# Smart_spectacles_for_drowsiness.net
KiCad netlist of a schematic drawn in EasyEDA
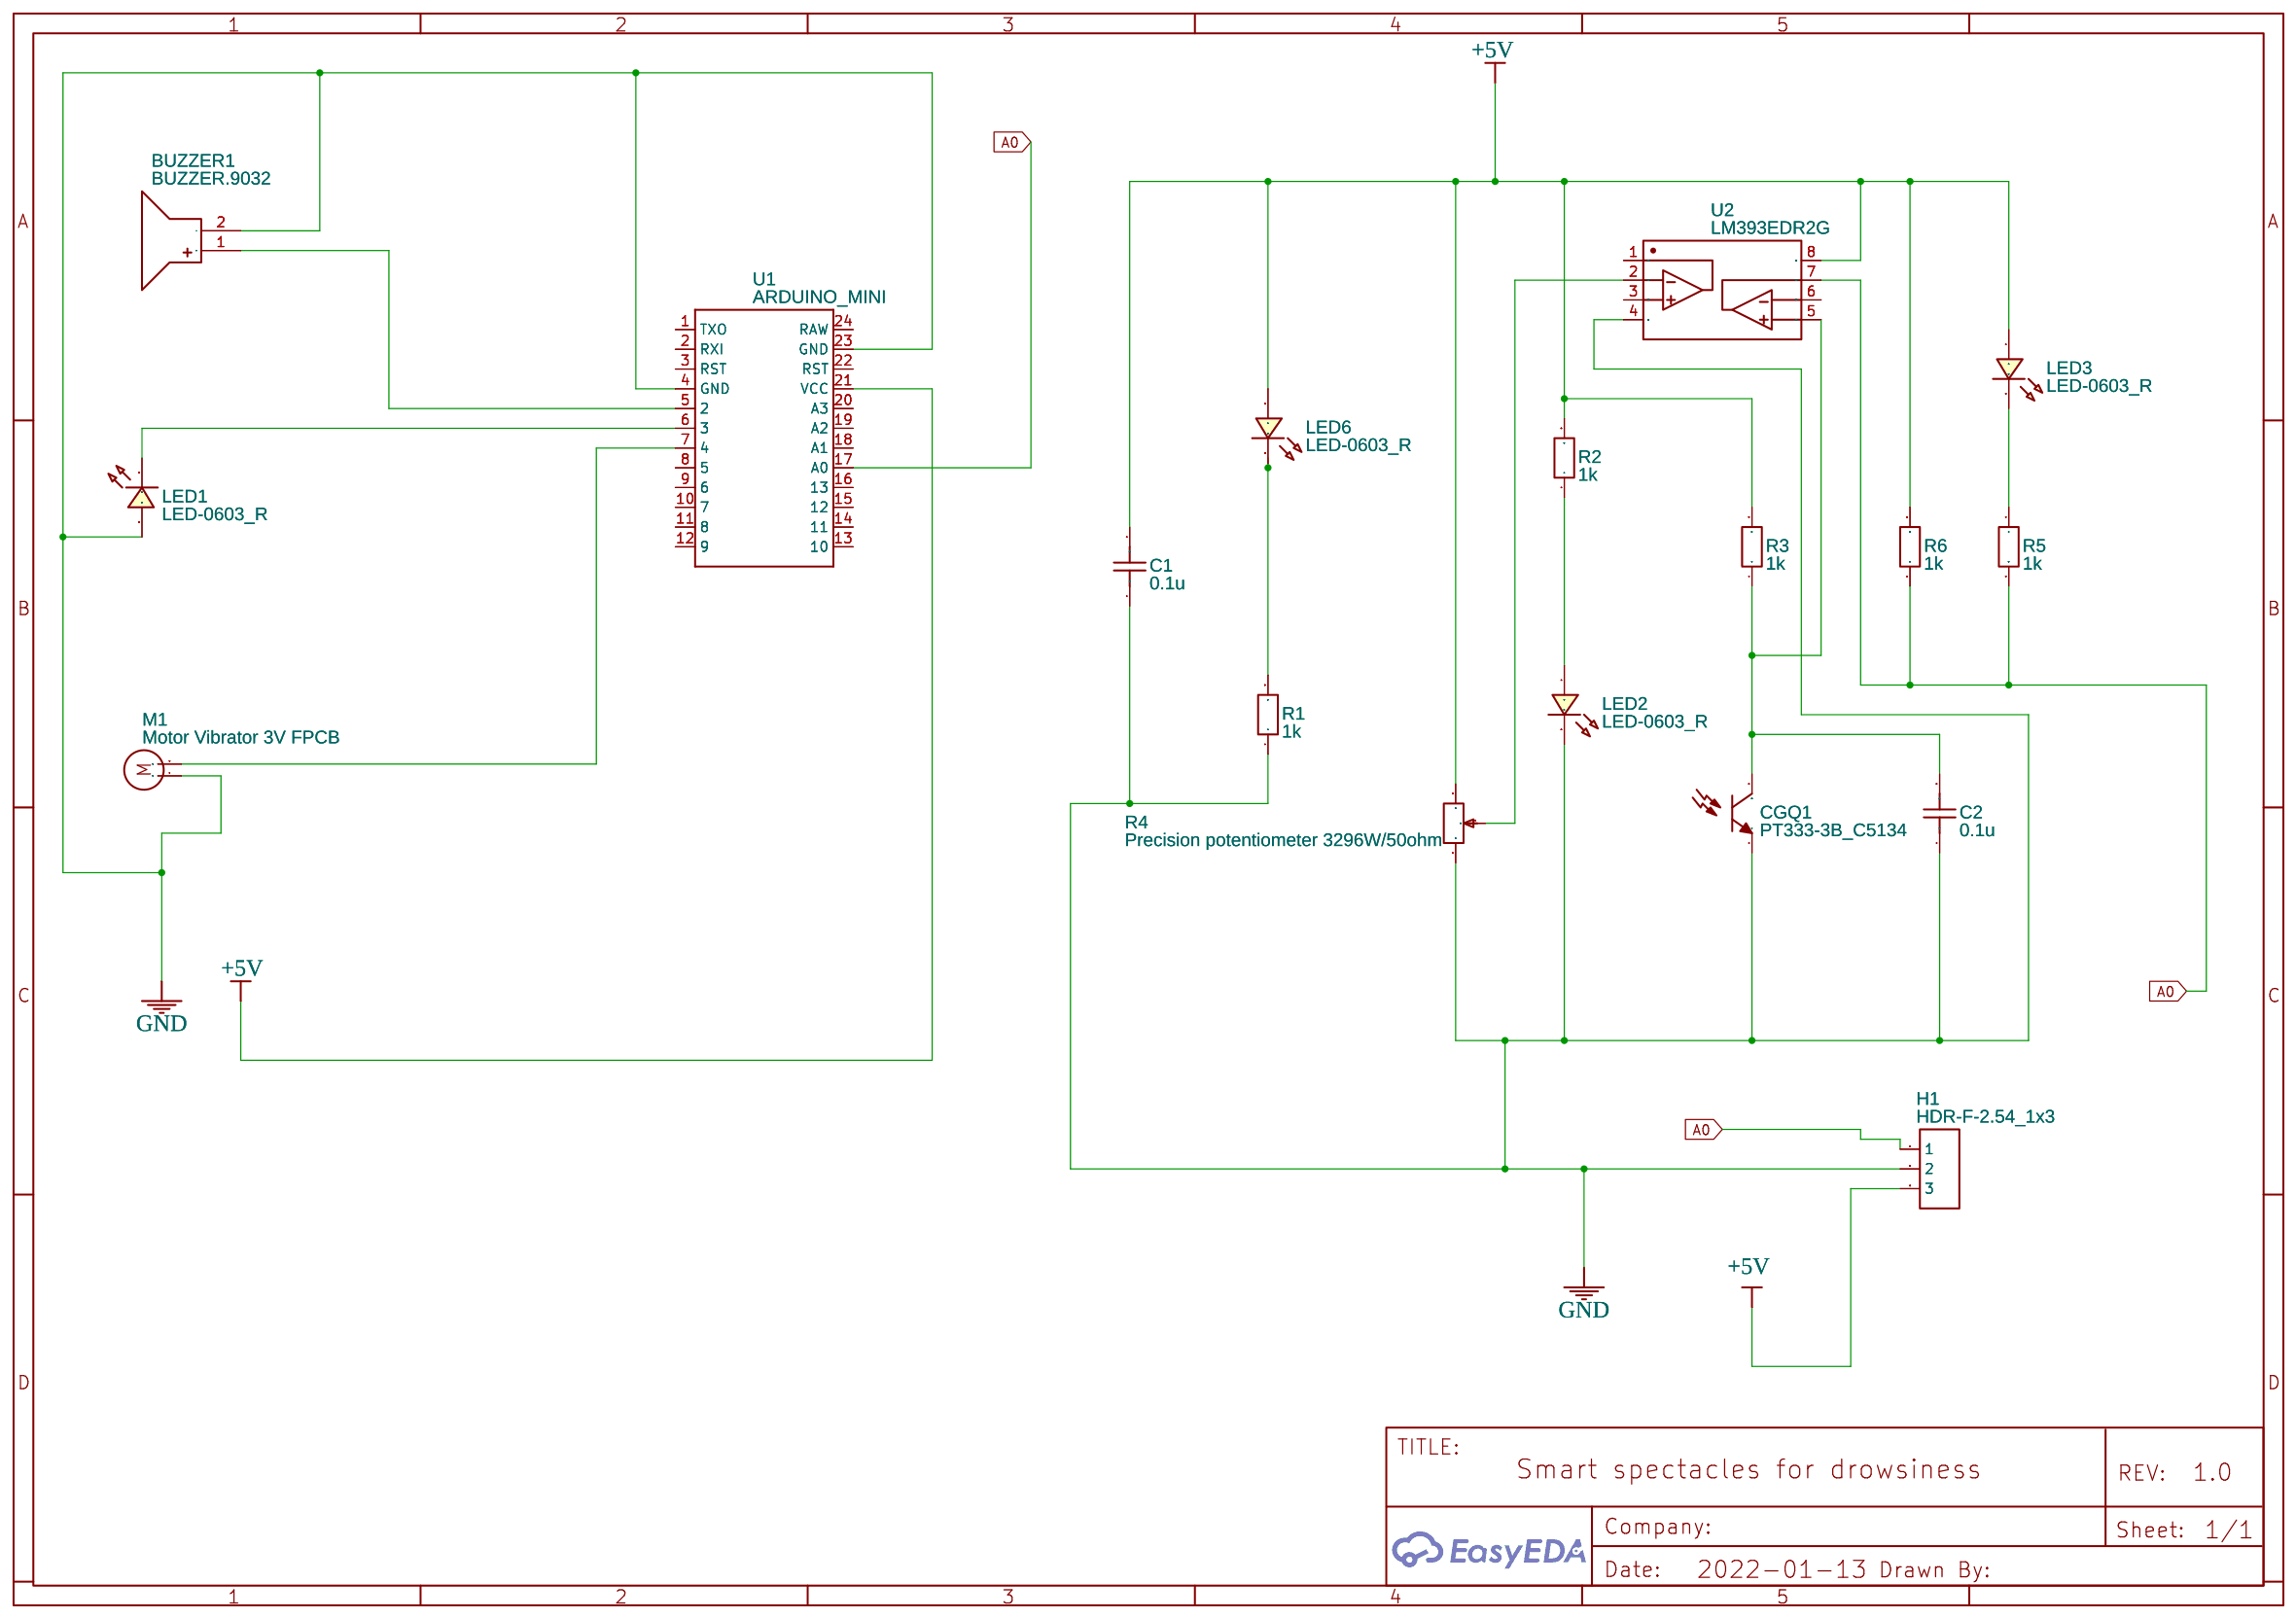
[diagram p0: schematic sheet]

(export (version "E")
  (design (tool "Eeschema 10.0.6"))
  (components
    (comp (ref "BUZZER1")
      (value "BUZZER.9032")
      (fields (field (name "BOM_Supplier Part") "C9900002564"))
      (libsource (lib "") (part "BUZZER.9032"))
    )
    (comp (ref "C1") (value "0.1u") (libsource (lib "") (part "C_0603_US")))
    (comp (ref "C2") (value "0.1u") (libsource (lib "") (part "C_0603_US")))
    (comp (ref "CGQ1")
      (value "PT333-3B_C5134")
      (fields (field (name "BOM_Manufacturer Part") "PT333-3B") (field (name "BOM_Supplier Part") "C5134"))
      (libsource (lib "") (part "PT333-3B_C5134"))
    )
    (comp (ref "H1")
      (value "HDR-F-2.54_1x3")
      (fields (field (name "BOM_Supplier Part") "C146690"))
      (libsource (lib "") (part "HDR-F-2.54_1x3"))
    )
    (comp (ref "LED1")
      (value "LED-0603_R")
      (fields
        (field (name "BOM_Manufacturer Part") "19-217/R6C-AL1M2VY/3T")
        (field (name "BOM_Supplier Part") "C72044")
      )
      (libsource (lib "") (part "LED-0603_R_1"))
    )
    (comp (ref "LED2")
      (value "LED-0603_R")
      (fields
        (field (name "BOM_Manufacturer Part") "19-217/R6C-AL1M2VY/3T")
        (field (name "BOM_Supplier Part") "C72044")
      )
      (libsource (lib "") (part "LED-0603_R"))
    )
    (comp (ref "LED3")
      (value "LED-0603_R")
      (fields
        (field (name "BOM_Manufacturer Part") "19-217/R6C-AL1M2VY/3T")
        (field (name "BOM_Supplier Part") "C72044")
      )
      (libsource (lib "") (part "LED-0603_R"))
    )
    (comp (ref "LED6")
      (value "LED-0603_R")
      (fields
        (field (name "BOM_Manufacturer Part") "19-217/R6C-AL1M2VY/3T")
        (field (name "BOM_Supplier Part") "C72044")
      )
      (libsource (lib "") (part "LED-0603_R"))
    )
    (comp (ref "M1")
      (value "Motor Vibrator 3V FPCB")
      (fields (field (name "BOM_Supplier Part") "C0827B020F"))
      (libsource (lib "") (part "Motor Vibrator 3V FPCB"))
    )
    (comp (ref "R1") (value "1k") (libsource (lib "") (part "R_0603_EU_1")))
    (comp (ref "R2") (value "1k") (libsource (lib "") (part "R_0603_EU_1")))
    (comp (ref "R3") (value "1k") (libsource (lib "") (part "R_0603_EU_1")))
    (comp (ref "R4")
      (value "Precision potentiometer 3296W/50ohm")
      (fields (field (name "BOM_Supplier Part") "C21881"))
      (libsource (lib "") (part "Precision potentiometer 3296W/50ohm"))
    )
    (comp (ref "R5") (value "1k") (libsource (lib "") (part "R_0603_EU")))
    (comp (ref "R6") (value "1k") (libsource (lib "") (part "R_0603_EU_1")))
    (comp (ref "U1") (value "ARDUINO_MINI") (libsource (lib "") (part "ARDUINO_MINI")))
    (comp (ref "U2")
      (value "LM393EDR2G")
      (fields (field (name "BOM_Supplier Part") "C152730"))
      (libsource (lib "") (part "LM393EDR2G"))
    )
  )
  (nets
    (net (code "1") (name "+5V") (class "Default")
      (node (ref "C1") (pin "2") (pinfunction "2_2") (pintype "unspecified"))
      (node (ref "H1") (pin "3") (pinfunction "3_3") (pintype "input"))
      (node (ref "LED3") (pin "1") (pinfunction "1_1") (pintype "unspecified"))
      (node (ref "LED6") (pin "1") (pinfunction "1_1") (pintype "unspecified"))
      (node (ref "R2") (pin "2") (pinfunction "2_2") (pintype "unspecified"))
      (node (ref "R3") (pin "2") (pinfunction "2_2") (pintype "unspecified"))
      (node (ref "R4") (pin "3") (pinfunction "3_3") (pintype "input"))
      (node (ref "R6") (pin "2") (pinfunction "2_2") (pintype "unspecified"))
      (node (ref "U1") (pin "21") (pinfunction "VCC_21") (pintype "unspecified"))
      (node (ref "U2") (pin "8") (pinfunction "VCC_8") (pintype "unspecified"))
    )
    (net (code "2") (name "A0") (class "Default")
      (node (ref "H1") (pin "1") (pinfunction "1_1") (pintype "input"))
      (node (ref "R5") (pin "2") (pinfunction "2_2") (pintype "unspecified"))
      (node (ref "R6") (pin "1") (pinfunction "1_1") (pintype "unspecified"))
      (node (ref "U1") (pin "17") (pinfunction "A0_17") (pintype "unspecified"))
      (node (ref "U2") (pin "7") (pinfunction "OUT2_7") (pintype "unspecified"))
    )
    (net (code "3") (name "GND") (class "Default")
      (node (ref "BUZZER1") (pin "2") (pinfunction "-_2") (pintype "unspecified"))
      (node (ref "C1") (pin "1") (pinfunction "1_1") (pintype "unspecified"))
      (node (ref "C2") (pin "1") (pinfunction "1_1") (pintype "unspecified"))
      (node (ref "CGQ1") (pin "1") (pinfunction "E_1") (pintype "unspecified"))
      (node (ref "H1") (pin "2") (pinfunction "2_2") (pintype "input"))
      (node (ref "LED1") (pin "1") (pinfunction "1_1") (pintype "unspecified"))
      (node (ref "LED2") (pin "2") (pinfunction "2_2") (pintype "unspecified"))
      (node (ref "M1") (pin "1") (pinfunction "1_1") (pintype "unspecified"))
      (node (ref "R1") (pin "1") (pinfunction "1_1") (pintype "unspecified"))
      (node (ref "R4") (pin "1") (pinfunction "1_1") (pintype "input"))
      (node (ref "U1") (pin "23") (pinfunction "GND_23") (pintype "unspecified"))
      (node (ref "U1") (pin "4") (pinfunction "GND_4") (pintype "unspecified"))
      (node (ref "U2") (pin "4") (pinfunction "GND_4") (pintype "unspecified"))
    )
    (net (code "4") (name "Net-(BUZZER1-+)") (class "Default")
      (node (ref "BUZZER1") (pin "1") (pinfunction "+_1") (pintype "unspecified"))
      (node (ref "U1") (pin "5") (pinfunction "2_5") (pintype "unspecified"))
    )
    (net (code "5") (name "Net-(CGQ1-C)") (class "Default")
      (node (ref "C2") (pin "2") (pinfunction "2_2") (pintype "unspecified"))
      (node (ref "CGQ1") (pin "2") (pinfunction "C_2") (pintype "unspecified"))
      (node (ref "R3") (pin "1") (pinfunction "1_1") (pintype "unspecified"))
      (node (ref "U2") (pin "5") (pinfunction "IN2+_5") (pintype "unspecified"))
    )
    (net (code "6") (name "Net-(LED2-Pad1)") (class "Default")
      (node (ref "LED2") (pin "1") (pinfunction "1_1") (pintype "unspecified"))
      (node (ref "R2") (pin "1") (pinfunction "1_1") (pintype "unspecified"))
    )
    (net (code "7") (name "Net-(LED3-Pad2)") (class "Default")
      (node (ref "LED3") (pin "2") (pinfunction "2_2") (pintype "unspecified"))
      (node (ref "R5") (pin "1") (pinfunction "1_1") (pintype "unspecified"))
    )
    (net (code "8") (name "Net-(LED6-Pad2)") (class "Default")
      (node (ref "LED6") (pin "2") (pinfunction "2_2") (pintype "unspecified"))
      (node (ref "R1") (pin "2") (pinfunction "2_2") (pintype "unspecified"))
    )
    (net (code "9") (name "Net-(U1-3)") (class "Default")
      (node (ref "LED1") (pin "2") (pinfunction "2_2") (pintype "unspecified"))
      (node (ref "U1") (pin "6") (pinfunction "3_6") (pintype "unspecified"))
    )
    (net (code "10") (name "Net-(U1-4)") (class "Default")
      (node (ref "M1") (pin "2") (pinfunction "2_2") (pintype "unspecified"))
      (node (ref "U1") (pin "7") (pinfunction "4_7") (pintype "unspecified"))
    )
    (net (code "11") (name "Net-(U2-IN1-)") (class "Default")
      (node (ref "R4") (pin "2") (pinfunction "2_2") (pintype "input"))
      (node (ref "U2") (pin "2") (pinfunction "IN1-_2") (pintype "unspecified"))
    )
    (net (code "12") (name "unconnected-(U1-5-Pad8)") (class "Default")
      (node (ref "U1") (pin "8") (pinfunction "5_8") (pintype "unspecified"))
    )
    (net (code "13") (name "unconnected-(U1-6-Pad9)") (class "Default")
      (node (ref "U1") (pin "9") (pinfunction "6_9") (pintype "unspecified"))
    )
    (net (code "14") (name "unconnected-(U1-7-Pad10)") (class "Default")
      (node (ref "U1") (pin "10") (pinfunction "7_10") (pintype "unspecified"))
    )
    (net (code "15") (name "unconnected-(U1-8-Pad11)") (class "Default")
      (node (ref "U1") (pin "11") (pinfunction "8_11") (pintype "unspecified"))
    )
    (net (code "16") (name "unconnected-(U1-9-Pad12)") (class "Default")
      (node (ref "U1") (pin "12") (pinfunction "9_12") (pintype "unspecified"))
    )
    (net (code "17") (name "unconnected-(U1-10-Pad13)") (class "Default")
      (node (ref "U1") (pin "13") (pinfunction "10_13") (pintype "unspecified"))
    )
    (net (code "18") (name "unconnected-(U1-11-Pad14)") (class "Default")
      (node (ref "U1") (pin "14") (pinfunction "11_14") (pintype "unspecified"))
    )
    (net (code "19") (name "unconnected-(U1-12-Pad15)") (class "Default")
      (node (ref "U1") (pin "15") (pinfunction "12_15") (pintype "unspecified"))
    )
    (net (code "20") (name "unconnected-(U1-13-Pad16)") (class "Default")
      (node (ref "U1") (pin "16") (pinfunction "13_16") (pintype "unspecified"))
    )
    (net (code "21") (name "unconnected-(U1-A1-Pad18)") (class "Default")
      (node (ref "U1") (pin "18") (pinfunction "A1_18") (pintype "unspecified"))
    )
    (net (code "22") (name "unconnected-(U1-A2-Pad19)") (class "Default")
      (node (ref "U1") (pin "19") (pinfunction "A2_19") (pintype "unspecified"))
    )
    (net (code "23") (name "unconnected-(U1-A3-Pad20)") (class "Default")
      (node (ref "U1") (pin "20") (pinfunction "A3_20") (pintype "unspecified"))
    )
    (net (code "24") (name "unconnected-(U1-RAW-Pad24)") (class "Default")
      (node (ref "U1") (pin "24") (pinfunction "RAW_24") (pintype "unspecified"))
    )
    (net (code "25") (name "unconnected-(U1-RST-Pad3)") (class "Default")
      (node (ref "U1") (pin "3") (pinfunction "RST_3") (pintype "unspecified"))
    )
    (net (code "26") (name "unconnected-(U1-RST-Pad22)") (class "Default")
      (node (ref "U1") (pin "22") (pinfunction "RST_22") (pintype "unspecified"))
    )
    (net (code "27") (name "unconnected-(U1-RXI-Pad2)") (class "Default")
      (node (ref "U1") (pin "2") (pinfunction "RXI_2") (pintype "unspecified"))
    )
    (net (code "28") (name "unconnected-(U1-TXO-Pad1)") (class "Default")
      (node (ref "U1") (pin "1") (pinfunction "TXO_1") (pintype "unspecified"))
    )
    (net (code "29") (name "unconnected-(U2-IN1+-Pad3)") (class "Default")
      (node (ref "U2") (pin "3") (pinfunction "IN1+_3") (pintype "unspecified"))
    )
    (net (code "30") (name "unconnected-(U2-IN2--Pad6)") (class "Default")
      (node (ref "U2") (pin "6") (pinfunction "IN2-_6") (pintype "unspecified"))
    )
    (net (code "31") (name "unconnected-(U2-OUT1-Pad1)") (class "Default")
      (node (ref "U2") (pin "1") (pinfunction "OUT1_1") (pintype "unspecified"))
    )
  )
)
